# ENABLE_MOSFETS.net
KiCad netlist of a schematic drawn in Altium Designer
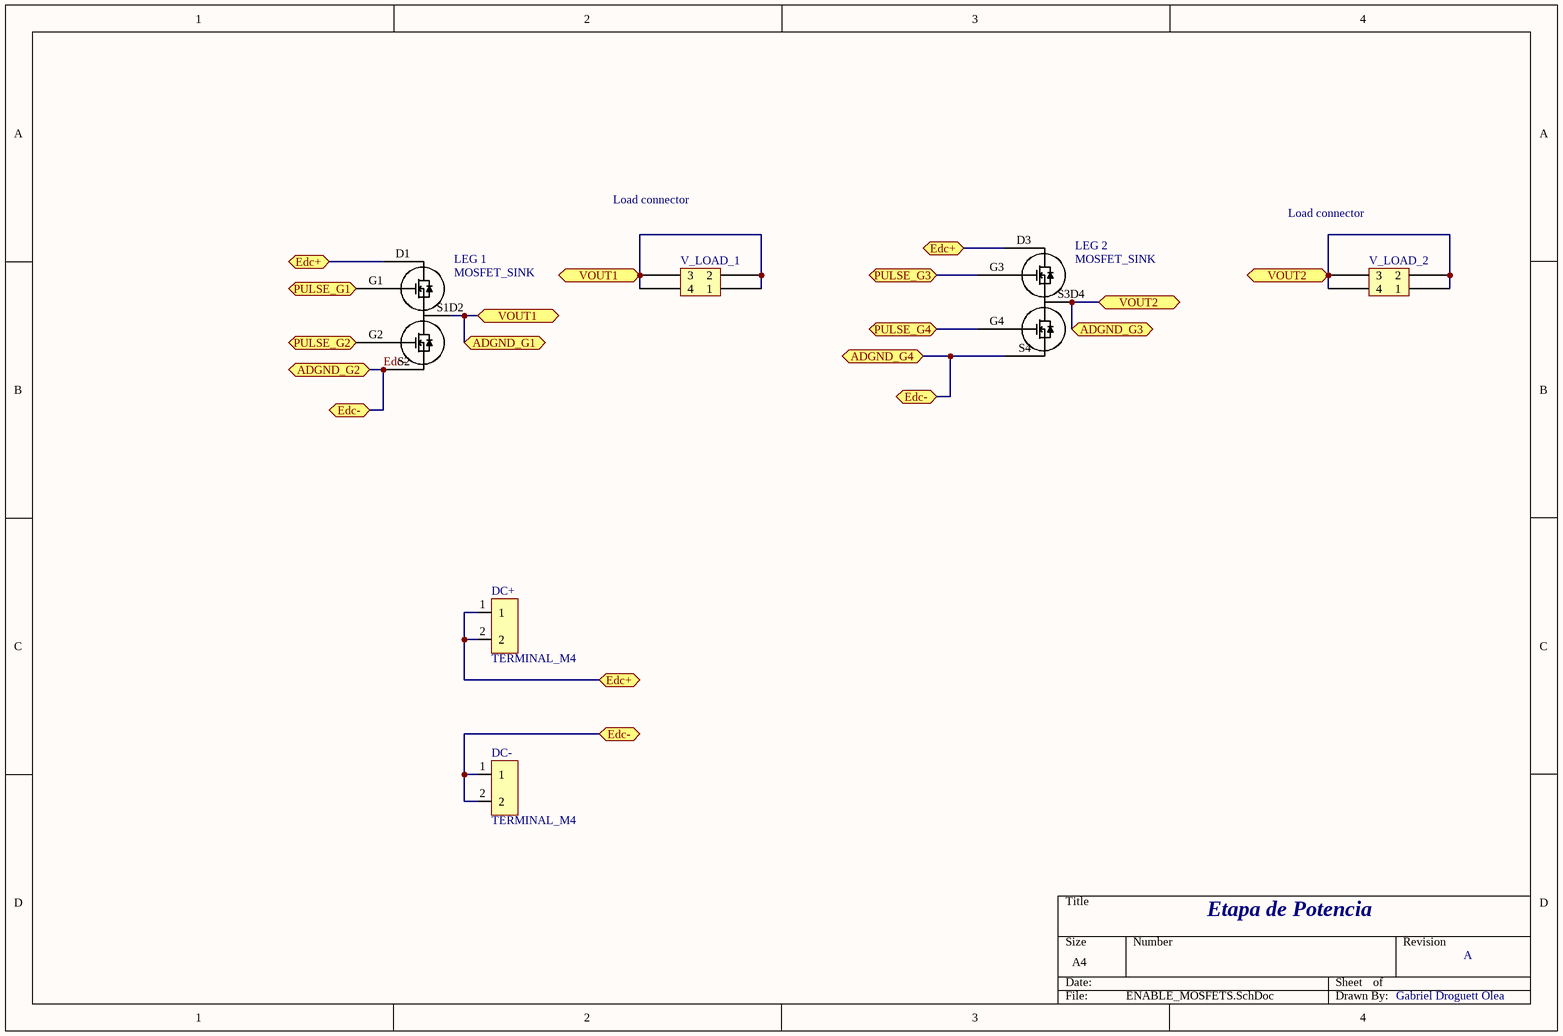
[diagram p0: ENABLE_MOSFETS.SchDoc]

(export (version "E")
  (design (tool "Eeschema 10.0.6"))
  (components
    (comp (ref "DC+")
      (value "TERMINAL_M4")
      (footprint "m4_6pin_screw")
      (fields
        (field (name "DIGI-KEY PART NUMBER") "A30603-ND")
        (field (name "MANUFACTURER PART NUMBER") "1586037-4")
      )
      (libsource (lib "CON_FASTON") (part "CON_FASTON"))
    )
    (comp (ref "DC-")
      (value "TERMINAL_M4")
      (footprint "m4_6pin_screw")
      (fields
        (field (name "DIGI-KEY PART NUMBER") "A30603-ND")
        (field (name "MANUFACTURER PART NUMBER") "1586037-4")
      )
      (libsource (lib "CON_FASTON") (part "CON_FASTON"))
    )
    (comp (ref "LEG 1")
      (value "MOSFET_SINK")
      (footprint "MOSFET-TO247_LEG_1")
      (description "HEATSINK FOR TO-247 TO-264 / CAMMING CLIP FOR TO-247")
      (fields
        (field (name "DIGI-KEY PART NUMBER") "C40-058-VE-ND")
        (field (name "MANUFACTURER PART NUMBER") "C40-058-VE")
      )
      (libsource (lib "aislados") (part "MOSFET_2_SINK_LEG_1"))
    )
    (comp (ref "LEG 2")
      (value "MOSFET_SINK")
      (footprint "MOSFET-TO247_LEG_2")
      (description "HEATSINK FOR TO-247 TO-264 / CAMMING CLIP FOR TO-247")
      (fields
        (field (name "DIGI-KEY PART NUMBER") "C40-058-VE-ND")
        (field (name "MANUFACTURER PART NUMBER") "C40-058-VE")
      )
      (libsource (lib "aislados") (part "MOSFET_2_SINK_LEG_2"))
    )
    (comp (ref "V_LOAD_1")
      (value "CONN HEADER 4POS")
      (footprint "Footprints_SOC (2):CONN HEADER 4POS")
      (description "CONN HEADER 4POS VERT W/O PEGS /  CONN RECEPT 4POS FREE HANGING")
      (fields
        (field (name "DIGI-KEY PART NUMBER") "732-1933-ND")
        (field (name "MANUFACTURER PART NUMBER") "64900429522")
      )
      (libsource (lib "aislados") (part "CONN HEADER 4POS"))
    )
    (comp (ref "V_LOAD_2")
      (value "CONN HEADER 4POS")
      (footprint "Footprints_SOC (2):CONN HEADER 4POS")
      (description "CONN HEADER 4POS VERT W/O PEGS /  CONN RECEPT 4POS FREE HANGING")
      (fields
        (field (name "DIGI-KEY PART NUMBER") "732-1933-ND")
        (field (name "MANUFACTURER PART NUMBER") "64900429522")
      )
      (libsource (lib "aislados") (part "CONN HEADER 4POS"))
    )
  )
  (nets
    (net (code "1") (name "/ADGND_G1") (class "Default")
      (node (ref "LEG 1") (pin "S1D2") (pinfunction "S1D2_S1D2") (pintype "passive"))
      (node (ref "V_LOAD_1") (pin "1") (pinfunction "1_1") (pintype "passive"))
      (node (ref "V_LOAD_1") (pin "2") (pinfunction "2_2") (pintype "passive"))
      (node (ref "V_LOAD_1") (pin "3") (pinfunction "3_3") (pintype "passive"))
      (node (ref "V_LOAD_1") (pin "4") (pinfunction "4_4") (pintype "passive"))
    )
    (net (code "2") (name "/ADGND_G3") (class "Default")
      (node (ref "LEG 2") (pin "S3D4") (pinfunction "S3D4_S3D4") (pintype "passive"))
      (node (ref "V_LOAD_2") (pin "1") (pinfunction "1_1") (pintype "passive"))
      (node (ref "V_LOAD_2") (pin "2") (pinfunction "2_2") (pintype "passive"))
      (node (ref "V_LOAD_2") (pin "3") (pinfunction "3_3") (pintype "passive"))
      (node (ref "V_LOAD_2") (pin "4") (pinfunction "4_4") (pintype "passive"))
    )
    (net (code "3") (name "/Edc+") (class "Default")
      (node (ref "DC+") (pin "1") (pinfunction "1_1") (pintype "passive"))
      (node (ref "DC+") (pin "2") (pinfunction "2_2") (pintype "passive"))
      (node (ref "LEG 1") (pin "D1") (pinfunction "D1_D1") (pintype "passive"))
      (node (ref "LEG 2") (pin "D3") (pinfunction "D3_D3") (pintype "passive"))
    )
    (net (code "4") (name "/Edc-") (class "Default")
      (node (ref "DC-") (pin "1") (pinfunction "1_1") (pintype "passive"))
      (node (ref "DC-") (pin "2") (pinfunction "2_2") (pintype "passive"))
      (node (ref "LEG 1") (pin "S2") (pinfunction "S2_S2") (pintype "passive"))
      (node (ref "LEG 2") (pin "S4") (pinfunction "S4_S4") (pintype "passive"))
    )
    (net (code "5") (name "/PULSE_G1") (class "Default")
      (node (ref "LEG 1") (pin "G1") (pinfunction "G1_G1") (pintype "passive"))
    )
    (net (code "6") (name "/PULSE_G2") (class "Default")
      (node (ref "LEG 1") (pin "G2") (pinfunction "G2_G2") (pintype "passive"))
    )
    (net (code "7") (name "/PULSE_G3") (class "Default")
      (node (ref "LEG 2") (pin "G3") (pinfunction "G3_G3") (pintype "passive"))
    )
    (net (code "8") (name "/PULSE_G4") (class "Default")
      (node (ref "LEG 2") (pin "G4") (pinfunction "G4_G4") (pintype "passive"))
    )
    (net (code "9") (name "unconnected-(LEG 1-PadD1)") (class "Default")
      (node (ref "LEG 1") (pin "D1") (pinfunction "D1_D1") (pintype "passive"))
    )
    (net (code "10") (name "unconnected-(LEG 1-PadG1)") (class "Default")
      (node (ref "LEG 1") (pin "G1") (pinfunction "G1_G1") (pintype "passive"))
    )
    (net (code "11") (name "unconnected-(LEG 1-PadG2)") (class "Default")
      (node (ref "LEG 1") (pin "G2") (pinfunction "G2_G2") (pintype "passive"))
    )
    (net (code "12") (name "unconnected-(LEG 1-PadS2)") (class "Default")
      (node (ref "LEG 1") (pin "S2") (pinfunction "S2_S2") (pintype "passive"))
    )
    (net (code "13") (name "unconnected-(LEG 2-PadD1)") (class "Default")
      (node (ref "LEG 2") (pin "D1") (pinfunction "D1_D1") (pintype "passive"))
    )
    (net (code "14") (name "unconnected-(LEG 2-PadG1)") (class "Default")
      (node (ref "LEG 2") (pin "G1") (pinfunction "G1_G1") (pintype "passive"))
    )
    (net (code "15") (name "unconnected-(LEG 2-PadG2)") (class "Default")
      (node (ref "LEG 2") (pin "G2") (pinfunction "G2_G2") (pintype "passive"))
    )
    (net (code "16") (name "unconnected-(LEG 2-PadS2)") (class "Default")
      (node (ref "LEG 2") (pin "S2") (pinfunction "S2_S2") (pintype "passive"))
    )
  )
)
